# LED_ring_V1.net
KiCad netlist of a schematic drawn in Altium Designer
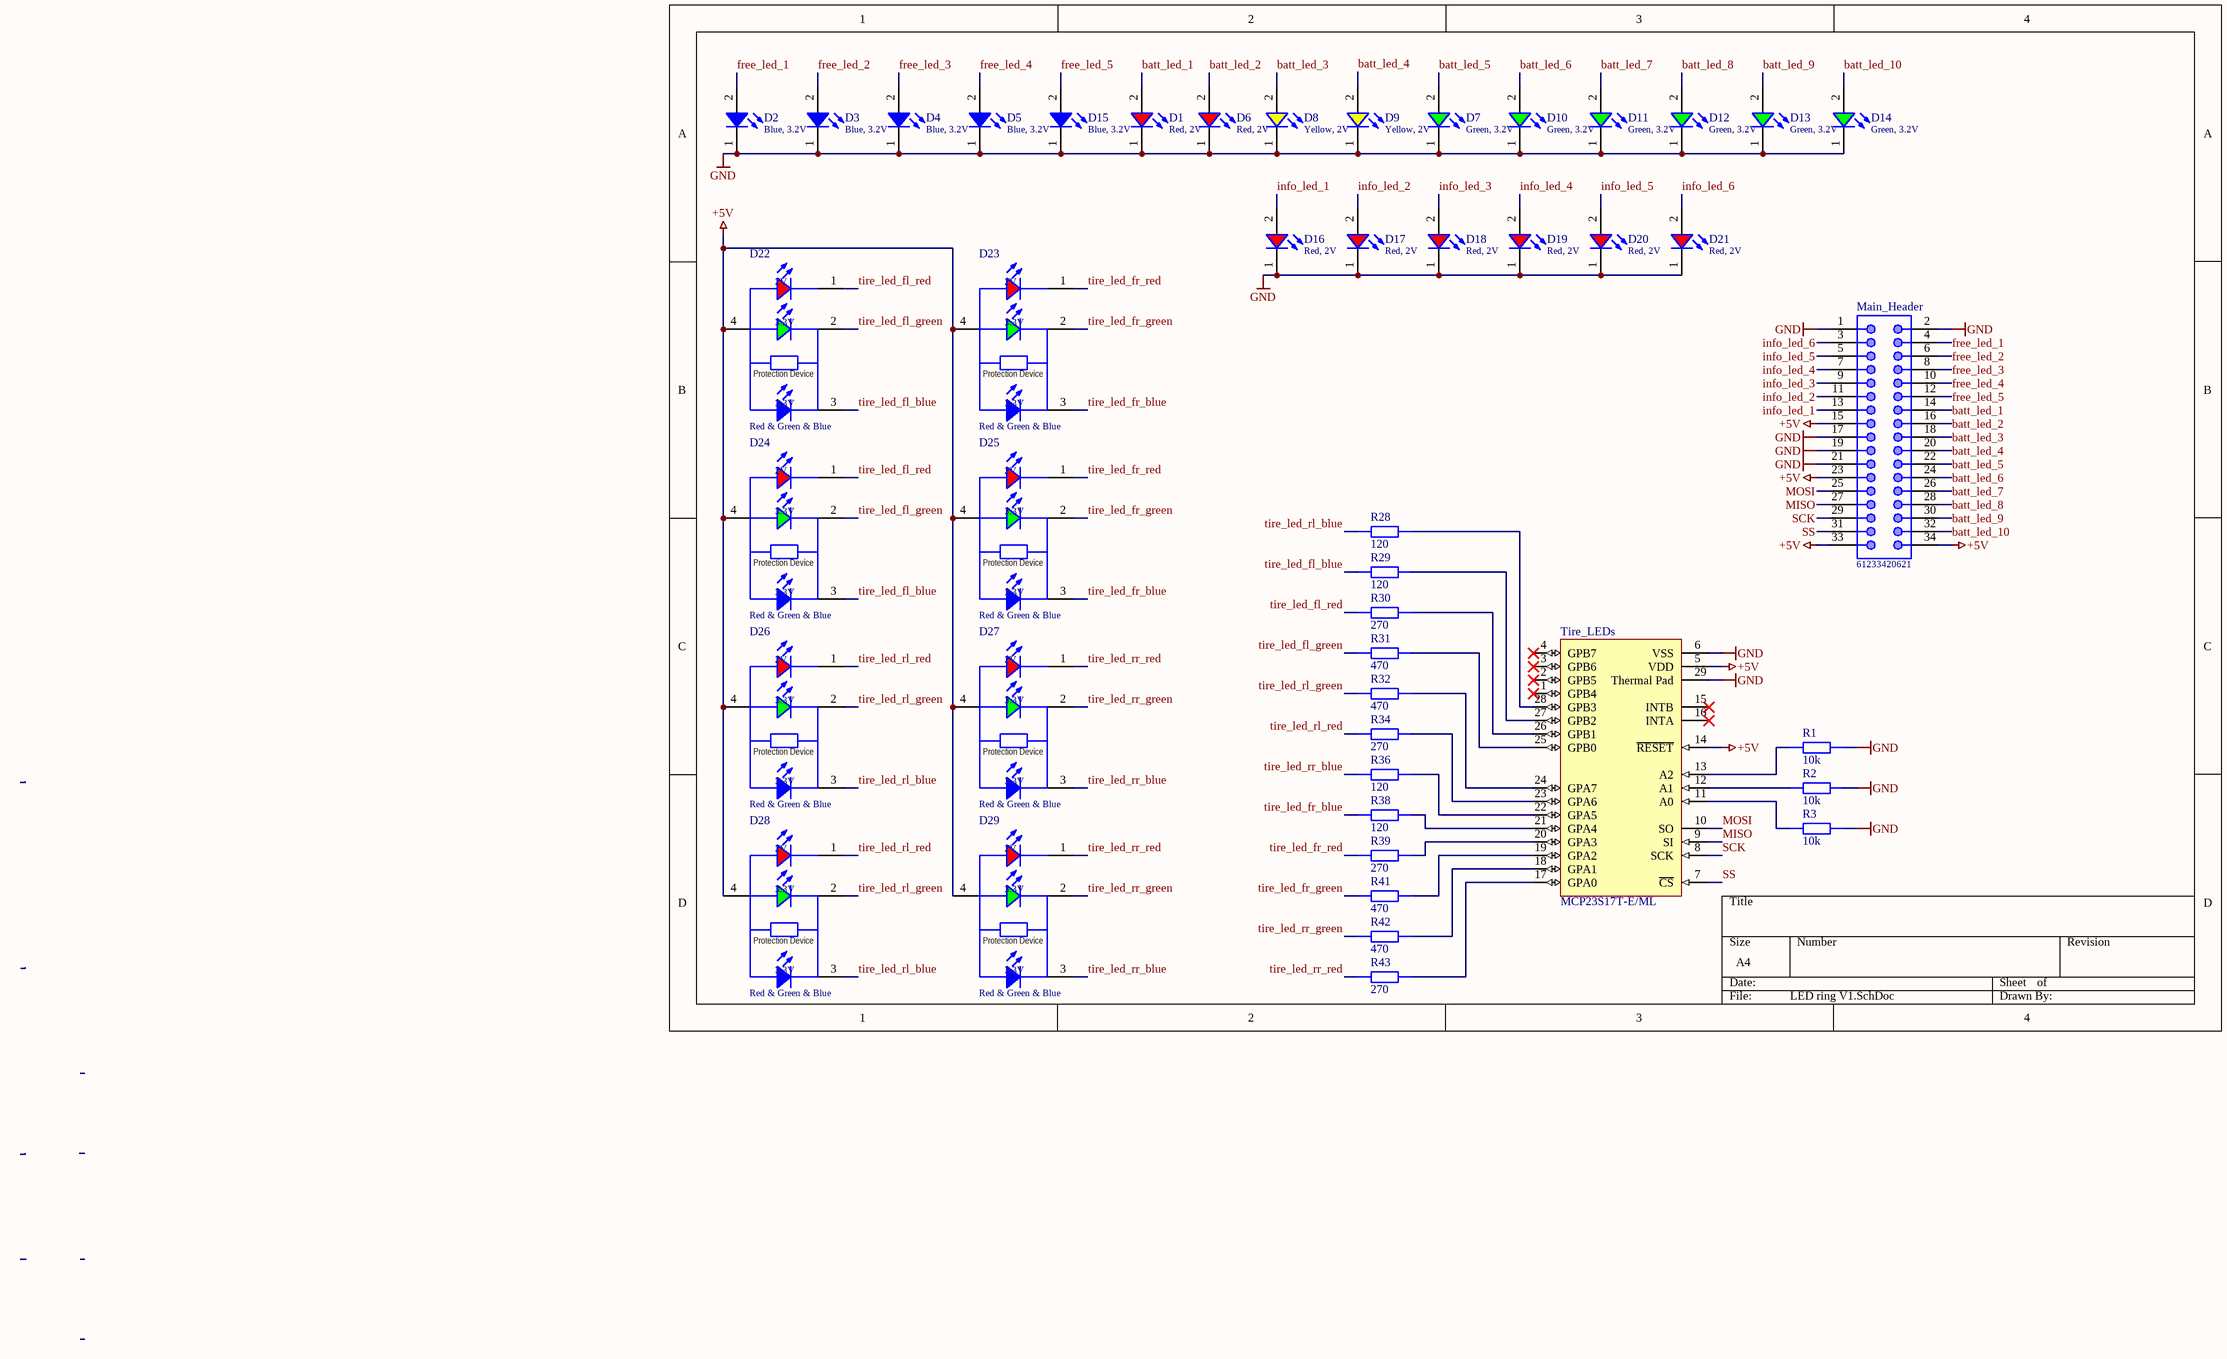
[diagram p0: LED ring V1.SchDoc]

(export (version "E")
  (design (tool "Eeschema 10.0.6"))
  (components
    (comp (ref "D1")
      (value "Red, 2V")
      (footprint "WL-SMCW_0805")
      (description "WL-SMCW SMT Mono-color Chip LED Waterclear, size 0805, Red, 2V, 140deg")
      (fields (field (name "PART NUMBER") "150080RS75000") (field (name "PUBLISHER") "Wurth Elektronik"))
      (libsource (lib "Altium_WL-SMCW (rev20a)") (part "150080RS75000"))
    )
    (comp (ref "D2")
      (value "Blue, 3.2V")
      (footprint "WL-SMCW_0805")
      (description "WL-SMCW SMT Mono-color Chip LED Waterclear, size 0805, Blue, 3.2V, 140deg")
      (fields (field (name "PART NUMBER") "150080BS75000") (field (name "PUBLISHER") "Wurth Elektronik"))
      (libsource (lib "Altium_WL-SMCW (rev20a)") (part "150080BS75000"))
    )
    (comp (ref "D3")
      (value "Blue, 3.2V")
      (footprint "WL-SMCW_0805")
      (description "WL-SMCW SMT Mono-color Chip LED Waterclear, size 0805, Blue, 3.2V, 140deg")
      (fields (field (name "PART NUMBER") "150080BS75000") (field (name "PUBLISHER") "Wurth Elektronik"))
      (libsource (lib "Altium_WL-SMCW (rev20a)") (part "150080BS75000"))
    )
    (comp (ref "D4")
      (value "Blue, 3.2V")
      (footprint "WL-SMCW_0805")
      (description "WL-SMCW SMT Mono-color Chip LED Waterclear, size 0805, Blue, 3.2V, 140deg")
      (fields (field (name "PART NUMBER") "150080BS75000") (field (name "PUBLISHER") "Wurth Elektronik"))
      (libsource (lib "Altium_WL-SMCW (rev20a)") (part "150080BS75000"))
    )
    (comp (ref "D5")
      (value "Blue, 3.2V")
      (footprint "WL-SMCW_0805")
      (description "WL-SMCW SMT Mono-color Chip LED Waterclear, size 0805, Blue, 3.2V, 140deg")
      (fields (field (name "PART NUMBER") "150080BS75000") (field (name "PUBLISHER") "Wurth Elektronik"))
      (libsource (lib "Altium_WL-SMCW (rev20a)") (part "150080BS75000"))
    )
    (comp (ref "D6")
      (value "Red, 2V")
      (footprint "WL-SMCW_0805")
      (description "WL-SMCW SMT Mono-color Chip LED Waterclear, size 0805, Red, 2V, 140deg")
      (fields (field (name "PART NUMBER") "150080RS75000") (field (name "PUBLISHER") "Wurth Elektronik"))
      (libsource (lib "Altium_WL-SMCW (rev20a)") (part "150080RS75000"))
    )
    (comp (ref "D7")
      (value "Green, 3.2V")
      (footprint "WL-SMCW_0805")
      (description "WL-SMCW SMT Mono-color Chip LED Waterclear, size 0805, Green, 3.2V, 140deg")
      (fields (field (name "PART NUMBER") "150080GS75000") (field (name "PUBLISHER") "Wurth Elektronik"))
      (libsource (lib "Altium_WL-SMCW (rev20a)") (part "150080GS75000"))
    )
    (comp (ref "D8")
      (value "Yellow, 2V")
      (footprint "WL-SMCW_0805")
      (description "WL-SMCW SMT Mono-color Chip LED Waterclear, size 0805, Yellow, 2V, 140deg")
      (fields (field (name "PART NUMBER") "150080YS75000") (field (name "PUBLISHER") "Wurth Elektronik"))
      (libsource (lib "Altium_WL-SMCW (rev20a)") (part "150080YS75000"))
    )
    (comp (ref "D9")
      (value "Yellow, 2V")
      (footprint "WL-SMCW_0805")
      (description "WL-SMCW SMT Mono-color Chip LED Waterclear, size 0805, Yellow, 2V, 140deg")
      (fields (field (name "PART NUMBER") "150080YS75000") (field (name "PUBLISHER") "Wurth Elektronik"))
      (libsource (lib "Altium_WL-SMCW (rev20a)") (part "150080YS75000"))
    )
    (comp (ref "D10")
      (value "Green, 3.2V")
      (footprint "WL-SMCW_0805")
      (description "WL-SMCW SMT Mono-color Chip LED Waterclear, size 0805, Green, 3.2V, 140deg")
      (fields (field (name "PART NUMBER") "150080GS75000") (field (name "PUBLISHER") "Wurth Elektronik"))
      (libsource (lib "Altium_WL-SMCW (rev20a)") (part "150080GS75000"))
    )
    (comp (ref "D11")
      (value "Green, 3.2V")
      (footprint "WL-SMCW_0805")
      (description "WL-SMCW SMT Mono-color Chip LED Waterclear, size 0805, Green, 3.2V, 140deg")
      (fields (field (name "PART NUMBER") "150080GS75000") (field (name "PUBLISHER") "Wurth Elektronik"))
      (libsource (lib "Altium_WL-SMCW (rev20a)") (part "150080GS75000"))
    )
    (comp (ref "D12")
      (value "Green, 3.2V")
      (footprint "WL-SMCW_0805")
      (description "WL-SMCW SMT Mono-color Chip LED Waterclear, size 0805, Green, 3.2V, 140deg")
      (fields (field (name "PART NUMBER") "150080GS75000") (field (name "PUBLISHER") "Wurth Elektronik"))
      (libsource (lib "Altium_WL-SMCW (rev20a)") (part "150080GS75000"))
    )
    (comp (ref "D13")
      (value "Green, 3.2V")
      (footprint "WL-SMCW_0805")
      (description "WL-SMCW SMT Mono-color Chip LED Waterclear, size 0805, Green, 3.2V, 140deg")
      (fields (field (name "PART NUMBER") "150080GS75000") (field (name "PUBLISHER") "Wurth Elektronik"))
      (libsource (lib "Altium_WL-SMCW (rev20a)") (part "150080GS75000"))
    )
    (comp (ref "D14")
      (value "Green, 3.2V")
      (footprint "WL-SMCW_0805")
      (description "WL-SMCW SMT Mono-color Chip LED Waterclear, size 0805, Green, 3.2V, 140deg")
      (fields (field (name "PART NUMBER") "150080GS75000") (field (name "PUBLISHER") "Wurth Elektronik"))
      (libsource (lib "Altium_WL-SMCW (rev20a)") (part "150080GS75000"))
    )
    (comp (ref "D15")
      (value "Blue, 3.2V")
      (footprint "WL-SMCW_0805")
      (description "WL-SMCW SMT Mono-color Chip LED Waterclear, size 0805, Blue, 3.2V, 140deg")
      (fields (field (name "PART NUMBER") "150080BS75000") (field (name "PUBLISHER") "Wurth Elektronik"))
      (libsource (lib "Altium_WL-SMCW (rev20a)") (part "150080BS75000"))
    )
    (comp (ref "D16")
      (value "Red, 2V")
      (footprint "WL-SMCW_0805")
      (description "WL-SMCW SMT Mono-color Chip LED Waterclear, size 0805, Red, 2V, 140deg")
      (fields (field (name "PART NUMBER") "150080RS75000") (field (name "PUBLISHER") "Wurth Elektronik"))
      (libsource (lib "Altium_WL-SMCW (rev20a)") (part "150080RS75000"))
    )
    (comp (ref "D17")
      (value "Red, 2V")
      (footprint "WL-SMCW_0805")
      (description "WL-SMCW SMT Mono-color Chip LED Waterclear, size 0805, Red, 2V, 140deg")
      (fields (field (name "PART NUMBER") "150080RS75000") (field (name "PUBLISHER") "Wurth Elektronik"))
      (libsource (lib "Altium_WL-SMCW (rev20a)") (part "150080RS75000"))
    )
    (comp (ref "D18")
      (value "Red, 2V")
      (footprint "WL-SMCW_0805")
      (description "WL-SMCW SMT Mono-color Chip LED Waterclear, size 0805, Red, 2V, 140deg")
      (fields (field (name "PART NUMBER") "150080RS75000") (field (name "PUBLISHER") "Wurth Elektronik"))
      (libsource (lib "Altium_WL-SMCW (rev20a)") (part "150080RS75000"))
    )
    (comp (ref "D19")
      (value "Red, 2V")
      (footprint "WL-SMCW_0805")
      (description "WL-SMCW SMT Mono-color Chip LED Waterclear, size 0805, Red, 2V, 140deg")
      (fields (field (name "PART NUMBER") "150080RS75000") (field (name "PUBLISHER") "Wurth Elektronik"))
      (libsource (lib "Altium_WL-SMCW (rev20a)") (part "150080RS75000"))
    )
    (comp (ref "D20")
      (value "Red, 2V")
      (footprint "WL-SMCW_0805")
      (description "WL-SMCW SMT Mono-color Chip LED Waterclear, size 0805, Red, 2V, 140deg")
      (fields (field (name "PART NUMBER") "150080RS75000") (field (name "PUBLISHER") "Wurth Elektronik"))
      (libsource (lib "Altium_WL-SMCW (rev20a)") (part "150080RS75000"))
    )
    (comp (ref "D21")
      (value "Red, 2V")
      (footprint "WL-SMCW_0805")
      (description "WL-SMCW SMT Mono-color Chip LED Waterclear, size 0805, Red, 2V, 140deg")
      (fields (field (name "PART NUMBER") "150080RS75000") (field (name "PUBLISHER") "Wurth Elektronik"))
      (libsource (lib "Altium_WL-SMCW (rev20a)") (part "150080RS75000"))
    )
    (comp (ref "D22")
      (value "Red & Green & Blue")
      (footprint "WL-SFCW_0805")
      (description "WL-SFCW SMT Full-color Chip LED Waterclear, size 0805, Red & Green & Blue, 120deg")
      (fields (field (name "PART NUMBER") "150080M173000") (field (name "PUBLISHER") "Wurth Elektronik"))
      (libsource (lib "Altium_WL-SFCW (rev19b)") (part "150080M173000"))
    )
    (comp (ref "D23")
      (value "Red & Green & Blue")
      (footprint "WL-SFCW_0805")
      (description "WL-SFCW SMT Full-color Chip LED Waterclear, size 0805, Red & Green & Blue, 120deg")
      (fields (field (name "PART NUMBER") "150080M173000") (field (name "PUBLISHER") "Wurth Elektronik"))
      (libsource (lib "Altium_WL-SFCW (rev19b)") (part "150080M173000"))
    )
    (comp (ref "D24")
      (value "Red & Green & Blue")
      (footprint "WL-SFCW_0805")
      (description "WL-SFCW SMT Full-color Chip LED Waterclear, size 0805, Red & Green & Blue, 120deg")
      (fields (field (name "PART NUMBER") "150080M173000") (field (name "PUBLISHER") "Wurth Elektronik"))
      (libsource (lib "Altium_WL-SFCW (rev19b)") (part "150080M173000"))
    )
    (comp (ref "D25")
      (value "Red & Green & Blue")
      (footprint "WL-SFCW_0805")
      (description "WL-SFCW SMT Full-color Chip LED Waterclear, size 0805, Red & Green & Blue, 120deg")
      (fields (field (name "PART NUMBER") "150080M173000") (field (name "PUBLISHER") "Wurth Elektronik"))
      (libsource (lib "Altium_WL-SFCW (rev19b)") (part "150080M173000"))
    )
    (comp (ref "D26")
      (value "Red & Green & Blue")
      (footprint "WL-SFCW_0805")
      (description "WL-SFCW SMT Full-color Chip LED Waterclear, size 0805, Red & Green & Blue, 120deg")
      (fields (field (name "PART NUMBER") "150080M173000") (field (name "PUBLISHER") "Wurth Elektronik"))
      (libsource (lib "Altium_WL-SFCW (rev19b)") (part "150080M173000"))
    )
    (comp (ref "D27")
      (value "Red & Green & Blue")
      (footprint "WL-SFCW_0805")
      (description "WL-SFCW SMT Full-color Chip LED Waterclear, size 0805, Red & Green & Blue, 120deg")
      (fields (field (name "PART NUMBER") "150080M173000") (field (name "PUBLISHER") "Wurth Elektronik"))
      (libsource (lib "Altium_WL-SFCW (rev19b)") (part "150080M173000"))
    )
    (comp (ref "D28")
      (value "Red & Green & Blue")
      (footprint "WL-SFCW_0805")
      (description "WL-SFCW SMT Full-color Chip LED Waterclear, size 0805, Red & Green & Blue, 120deg")
      (fields (field (name "PART NUMBER") "150080M173000") (field (name "PUBLISHER") "Wurth Elektronik"))
      (libsource (lib "Altium_WL-SFCW (rev19b)") (part "150080M173000"))
    )
    (comp (ref "D29")
      (value "Red & Green & Blue")
      (footprint "WL-SFCW_0805")
      (description "WL-SFCW SMT Full-color Chip LED Waterclear, size 0805, Red & Green & Blue, 120deg")
      (fields (field (name "PART NUMBER") "150080M173000") (field (name "PUBLISHER") "Wurth Elektronik"))
      (libsource (lib "Altium_WL-SFCW (rev19b)") (part "150080M173000"))
    )
    (comp (ref "Main_Header")
      (value "61233420621")
      (footprint "61233420621")
      (description "WR-BHD Box Header, Male PCB side, pitch 2.54mm, SMT, Straight, 34p")
      (fields (field (name "MANUFACTURER") "Wurth Elektronik"))
      (libsource (lib "Altium_WR-BHD (rev21a)") (part "61233420621"))
    )
    (comp (ref "R1")
      (value "10k")
      (footprint "STACKPOLE CSR0603")
      (description "Resistor with multiple footprints")
      (fields (field (name "Comment") "SMD Resistor"))
      (libsource (lib "Standardbauteile") (part "SMD Resistor"))
    )
    (comp (ref "R2")
      (value "10k")
      (footprint "STACKPOLE CSR0603")
      (description "Resistor with multiple footprints")
      (fields (field (name "Comment") "SMD Resistor"))
      (libsource (lib "Standardbauteile") (part "SMD Resistor"))
    )
    (comp (ref "R3")
      (value "10k")
      (footprint "STACKPOLE CSR0603")
      (description "Resistor with multiple footprints")
      (fields (field (name "Comment") "SMD Resistor"))
      (libsource (lib "Standardbauteile") (part "SMD Resistor"))
    )
    (comp (ref "R28")
      (value "120")
      (footprint "STACKPOLE CSR0603")
      (description "Resistor with multiple footprints")
      (fields (field (name "Comment") "SMD Resistor"))
      (libsource (lib "Standardbauteile") (part "SMD Resistor"))
    )
    (comp (ref "R29")
      (value "120")
      (footprint "STACKPOLE CSR0603")
      (description "Resistor with multiple footprints")
      (fields (field (name "Comment") "SMD Resistor"))
      (libsource (lib "Standardbauteile") (part "SMD Resistor"))
    )
    (comp (ref "R30")
      (value "270")
      (footprint "STACKPOLE CSR0603")
      (description "Resistor with multiple footprints")
      (fields (field (name "Comment") "SMD Resistor"))
      (libsource (lib "Standardbauteile") (part "SMD Resistor"))
    )
    (comp (ref "R31")
      (value "470")
      (footprint "STACKPOLE CSR0603")
      (description "Resistor with multiple footprints")
      (fields (field (name "Comment") "SMD Resistor"))
      (libsource (lib "Standardbauteile") (part "SMD Resistor"))
    )
    (comp (ref "R32")
      (value "470")
      (footprint "STACKPOLE CSR0603")
      (description "Resistor with multiple footprints")
      (fields (field (name "Comment") "SMD Resistor"))
      (libsource (lib "Standardbauteile") (part "SMD Resistor"))
    )
    (comp (ref "R34")
      (value "270")
      (footprint "STACKPOLE CSR0603")
      (description "Resistor with multiple footprints")
      (fields (field (name "Comment") "SMD Resistor"))
      (libsource (lib "Standardbauteile") (part "SMD Resistor"))
    )
    (comp (ref "R36")
      (value "120")
      (footprint "STACKPOLE CSR0603")
      (description "Resistor with multiple footprints")
      (fields (field (name "Comment") "SMD Resistor"))
      (libsource (lib "Standardbauteile") (part "SMD Resistor"))
    )
    (comp (ref "R38")
      (value "120")
      (footprint "STACKPOLE CSR0603")
      (description "Resistor with multiple footprints")
      (fields (field (name "Comment") "SMD Resistor"))
      (libsource (lib "Standardbauteile") (part "SMD Resistor"))
    )
    (comp (ref "R39")
      (value "270")
      (footprint "STACKPOLE CSR0603")
      (description "Resistor with multiple footprints")
      (fields (field (name "Comment") "SMD Resistor"))
      (libsource (lib "Standardbauteile") (part "SMD Resistor"))
    )
    (comp (ref "R41")
      (value "470")
      (footprint "STACKPOLE CSR0603")
      (description "Resistor with multiple footprints")
      (fields (field (name "Comment") "SMD Resistor"))
      (libsource (lib "Standardbauteile") (part "SMD Resistor"))
    )
    (comp (ref "R42")
      (value "470")
      (footprint "STACKPOLE CSR0603")
      (description "Resistor with multiple footprints")
      (fields (field (name "Comment") "SMD Resistor"))
      (libsource (lib "Standardbauteile") (part "SMD Resistor"))
    )
    (comp (ref "R43")
      (value "270")
      (footprint "STACKPOLE CSR0603")
      (description "Resistor with multiple footprints")
      (fields (field (name "Comment") "SMD Resistor"))
      (libsource (lib "Standardbauteile") (part "SMD Resistor"))
    )
    (comp (ref "Tire_LEDs")
      (value "MCP23S17T-E/ML")
      (footprint "QFN-ML28_M")
      (description "16-Bit I/O Expander with Serial Interface, 28-Pin QFN, Extended Temperature, Tape and Reel")
      (libsource (lib "Altium Content Vault") (part "PR-BUSIC-MCP23S17-29"))
    )
  )
  (nets
    (net (code "1") (name "+5V") (class "Default")
      (node (ref "D22") (pin "4") (pinfunction "A_4") (pintype "passive"))
      (node (ref "D23") (pin "4") (pinfunction "A_4") (pintype "passive"))
      (node (ref "D24") (pin "4") (pinfunction "A_4") (pintype "passive"))
      (node (ref "D25") (pin "4") (pinfunction "A_4") (pintype "passive"))
      (node (ref "D26") (pin "4") (pinfunction "A_4") (pintype "passive"))
      (node (ref "D27") (pin "4") (pinfunction "A_4") (pintype "passive"))
      (node (ref "D28") (pin "4") (pinfunction "A_4") (pintype "passive"))
      (node (ref "D29") (pin "4") (pinfunction "A_4") (pintype "passive"))
      (node (ref "Main_Header") (pin "15") (pinfunction "15_15") (pintype "passive"))
      (node (ref "Main_Header") (pin "23") (pinfunction "23_23") (pintype "passive"))
      (node (ref "Main_Header") (pin "33") (pinfunction "33_33") (pintype "passive"))
      (node (ref "Main_Header") (pin "34") (pinfunction "34_34") (pintype "passive"))
      (node (ref "Tire_LEDs") (pin "14") (pinfunction "~{RESET}_14") (pintype "input"))
      (node (ref "Tire_LEDs") (pin "5") (pinfunction "VDD_5") (pintype "power_in"))
    )
    (net (code "2") (name "/MISO") (class "Default")
      (node (ref "Main_Header") (pin "27") (pinfunction "27_27") (pintype "passive"))
      (node (ref "Tire_LEDs") (pin "9") (pinfunction "SI_9") (pintype "input"))
    )
    (net (code "3") (name "/MOSI") (class "Default")
      (node (ref "Main_Header") (pin "25") (pinfunction "25_25") (pintype "passive"))
      (node (ref "Tire_LEDs") (pin "10") (pinfunction "SO_10") (pintype "tri_state"))
    )
    (net (code "4") (name "/SCK") (class "Default")
      (node (ref "Main_Header") (pin "29") (pinfunction "29_29") (pintype "passive"))
      (node (ref "Tire_LEDs") (pin "8") (pinfunction "SCK_8") (pintype "input"))
    )
    (net (code "5") (name "/SS") (class "Default")
      (node (ref "Main_Header") (pin "31") (pinfunction "31_31") (pintype "passive"))
      (node (ref "Tire_LEDs") (pin "7") (pinfunction "~{CS}_7") (pintype "input"))
    )
    (net (code "6") (name "/batt_led_1") (class "Default")
      (node (ref "D1") (pin "2") (pinfunction "A_2") (pintype "passive"))
      (node (ref "Main_Header") (pin "14") (pinfunction "14_14") (pintype "passive"))
    )
    (net (code "7") (name "/batt_led_2") (class "Default")
      (node (ref "D6") (pin "2") (pinfunction "A_2") (pintype "passive"))
      (node (ref "Main_Header") (pin "16") (pinfunction "16_16") (pintype "passive"))
    )
    (net (code "8") (name "/batt_led_3") (class "Default")
      (node (ref "D8") (pin "2") (pinfunction "A_2") (pintype "passive"))
      (node (ref "Main_Header") (pin "18") (pinfunction "18_18") (pintype "passive"))
    )
    (net (code "9") (name "/batt_led_4") (class "Default")
      (node (ref "D9") (pin "2") (pinfunction "A_2") (pintype "passive"))
      (node (ref "Main_Header") (pin "20") (pinfunction "20_20") (pintype "passive"))
    )
    (net (code "10") (name "/batt_led_5") (class "Default")
      (node (ref "D7") (pin "2") (pinfunction "A_2") (pintype "passive"))
      (node (ref "Main_Header") (pin "22") (pinfunction "22_22") (pintype "passive"))
    )
    (net (code "11") (name "/batt_led_6") (class "Default")
      (node (ref "D10") (pin "2") (pinfunction "A_2") (pintype "passive"))
      (node (ref "Main_Header") (pin "24") (pinfunction "24_24") (pintype "passive"))
    )
    (net (code "12") (name "/batt_led_7") (class "Default")
      (node (ref "D11") (pin "2") (pinfunction "A_2") (pintype "passive"))
      (node (ref "Main_Header") (pin "26") (pinfunction "26_26") (pintype "passive"))
    )
    (net (code "13") (name "/batt_led_8") (class "Default")
      (node (ref "D12") (pin "2") (pinfunction "A_2") (pintype "passive"))
      (node (ref "Main_Header") (pin "28") (pinfunction "28_28") (pintype "passive"))
    )
    (net (code "14") (name "/batt_led_9") (class "Default")
      (node (ref "D13") (pin "2") (pinfunction "A_2") (pintype "passive"))
      (node (ref "Main_Header") (pin "30") (pinfunction "30_30") (pintype "passive"))
    )
    (net (code "15") (name "/batt_led_10") (class "Default")
      (node (ref "D14") (pin "2") (pinfunction "A_2") (pintype "passive"))
      (node (ref "Main_Header") (pin "32") (pinfunction "32_32") (pintype "passive"))
    )
    (net (code "16") (name "/free_led_1") (class "Default")
      (node (ref "D2") (pin "2") (pinfunction "A_2") (pintype "passive"))
      (node (ref "Main_Header") (pin "4") (pinfunction "4_4") (pintype "passive"))
    )
    (net (code "17") (name "/free_led_2") (class "Default")
      (node (ref "D3") (pin "2") (pinfunction "A_2") (pintype "passive"))
      (node (ref "Main_Header") (pin "6") (pinfunction "6_6") (pintype "passive"))
    )
    (net (code "18") (name "/free_led_3") (class "Default")
      (node (ref "D4") (pin "2") (pinfunction "A_2") (pintype "passive"))
      (node (ref "Main_Header") (pin "8") (pinfunction "8_8") (pintype "passive"))
    )
    (net (code "19") (name "/free_led_4") (class "Default")
      (node (ref "D5") (pin "2") (pinfunction "A_2") (pintype "passive"))
      (node (ref "Main_Header") (pin "10") (pinfunction "10_10") (pintype "passive"))
    )
    (net (code "20") (name "/free_led_5") (class "Default")
      (node (ref "D15") (pin "2") (pinfunction "A_2") (pintype "passive"))
      (node (ref "Main_Header") (pin "12") (pinfunction "12_12") (pintype "passive"))
    )
    (net (code "21") (name "/info_led_1") (class "Default")
      (node (ref "D16") (pin "2") (pinfunction "A_2") (pintype "passive"))
      (node (ref "Main_Header") (pin "13") (pinfunction "13_13") (pintype "passive"))
    )
    (net (code "22") (name "/info_led_2") (class "Default")
      (node (ref "D17") (pin "2") (pinfunction "A_2") (pintype "passive"))
      (node (ref "Main_Header") (pin "11") (pinfunction "11_11") (pintype "passive"))
    )
    (net (code "23") (name "/info_led_3") (class "Default")
      (node (ref "D18") (pin "2") (pinfunction "A_2") (pintype "passive"))
      (node (ref "Main_Header") (pin "9") (pinfunction "9_9") (pintype "passive"))
    )
    (net (code "24") (name "/info_led_4") (class "Default")
      (node (ref "D19") (pin "2") (pinfunction "A_2") (pintype "passive"))
      (node (ref "Main_Header") (pin "7") (pinfunction "7_7") (pintype "passive"))
    )
    (net (code "25") (name "/info_led_5") (class "Default")
      (node (ref "D20") (pin "2") (pinfunction "A_2") (pintype "passive"))
      (node (ref "Main_Header") (pin "5") (pinfunction "5_5") (pintype "passive"))
    )
    (net (code "26") (name "/info_led_6") (class "Default")
      (node (ref "D21") (pin "2") (pinfunction "A_2") (pintype "passive"))
      (node (ref "Main_Header") (pin "3") (pinfunction "3_3") (pintype "passive"))
    )
    (net (code "27") (name "/tire_led_fl_blue") (class "Default")
      (node (ref "D22") (pin "3") (pinfunction "K_3") (pintype "passive"))
      (node (ref "D24") (pin "3") (pinfunction "K_3") (pintype "passive"))
      (node (ref "R29") (pin "2") (pinfunction "2_2") (pintype "passive"))
    )
    (net (code "28") (name "/tire_led_fl_green") (class "Default")
      (node (ref "D22") (pin "2") (pinfunction "K_2") (pintype "passive"))
      (node (ref "D24") (pin "2") (pinfunction "K_2") (pintype "passive"))
      (node (ref "R31") (pin "2") (pinfunction "2_2") (pintype "passive"))
    )
    (net (code "29") (name "/tire_led_fl_red") (class "Default")
      (node (ref "D22") (pin "1") (pinfunction "K_1") (pintype "passive"))
      (node (ref "D24") (pin "1") (pinfunction "K_1") (pintype "passive"))
      (node (ref "R30") (pin "2") (pinfunction "2_2") (pintype "passive"))
    )
    (net (code "30") (name "/tire_led_fr_blue") (class "Default")
      (node (ref "D23") (pin "3") (pinfunction "K_3") (pintype "passive"))
      (node (ref "D25") (pin "3") (pinfunction "K_3") (pintype "passive"))
      (node (ref "R38") (pin "2") (pinfunction "2_2") (pintype "passive"))
    )
    (net (code "31") (name "/tire_led_fr_green") (class "Default")
      (node (ref "D23") (pin "2") (pinfunction "K_2") (pintype "passive"))
      (node (ref "D25") (pin "2") (pinfunction "K_2") (pintype "passive"))
      (node (ref "R41") (pin "2") (pinfunction "2_2") (pintype "passive"))
    )
    (net (code "32") (name "/tire_led_fr_red") (class "Default")
      (node (ref "D23") (pin "1") (pinfunction "K_1") (pintype "passive"))
      (node (ref "D25") (pin "1") (pinfunction "K_1") (pintype "passive"))
      (node (ref "R39") (pin "2") (pinfunction "2_2") (pintype "passive"))
    )
    (net (code "33") (name "/tire_led_rl_blue") (class "Default")
      (node (ref "D26") (pin "3") (pinfunction "K_3") (pintype "passive"))
      (node (ref "D28") (pin "3") (pinfunction "K_3") (pintype "passive"))
      (node (ref "R28") (pin "2") (pinfunction "2_2") (pintype "passive"))
    )
    (net (code "34") (name "/tire_led_rl_green") (class "Default")
      (node (ref "D26") (pin "2") (pinfunction "K_2") (pintype "passive"))
      (node (ref "D28") (pin "2") (pinfunction "K_2") (pintype "passive"))
      (node (ref "R32") (pin "2") (pinfunction "2_2") (pintype "passive"))
    )
    (net (code "35") (name "/tire_led_rl_red") (class "Default")
      (node (ref "D26") (pin "1") (pinfunction "K_1") (pintype "passive"))
      (node (ref "D28") (pin "1") (pinfunction "K_1") (pintype "passive"))
      (node (ref "R34") (pin "2") (pinfunction "2_2") (pintype "passive"))
    )
    (net (code "36") (name "/tire_led_rr_blue") (class "Default")
      (node (ref "D27") (pin "3") (pinfunction "K_3") (pintype "passive"))
      (node (ref "D29") (pin "3") (pinfunction "K_3") (pintype "passive"))
      (node (ref "R36") (pin "2") (pinfunction "2_2") (pintype "passive"))
    )
    (net (code "37") (name "/tire_led_rr_green") (class "Default")
      (node (ref "D27") (pin "2") (pinfunction "K_2") (pintype "passive"))
      (node (ref "D29") (pin "2") (pinfunction "K_2") (pintype "passive"))
      (node (ref "R42") (pin "2") (pinfunction "2_2") (pintype "passive"))
    )
    (net (code "38") (name "/tire_led_rr_red") (class "Default")
      (node (ref "D27") (pin "1") (pinfunction "K_1") (pintype "passive"))
      (node (ref "D29") (pin "1") (pinfunction "K_1") (pintype "passive"))
      (node (ref "R43") (pin "2") (pinfunction "2_2") (pintype "passive"))
    )
    (net (code "39") (name "GND") (class "Default")
      (node (ref "D1") (pin "1") (pinfunction "K_1") (pintype "passive"))
      (node (ref "D10") (pin "1") (pinfunction "K_1") (pintype "passive"))
      (node (ref "D11") (pin "1") (pinfunction "K_1") (pintype "passive"))
      (node (ref "D12") (pin "1") (pinfunction "K_1") (pintype "passive"))
      (node (ref "D13") (pin "1") (pinfunction "K_1") (pintype "passive"))
      (node (ref "D14") (pin "1") (pinfunction "K_1") (pintype "passive"))
      (node (ref "D15") (pin "1") (pinfunction "K_1") (pintype "passive"))
      (node (ref "D16") (pin "1") (pinfunction "K_1") (pintype "passive"))
      (node (ref "D17") (pin "1") (pinfunction "K_1") (pintype "passive"))
      (node (ref "D18") (pin "1") (pinfunction "K_1") (pintype "passive"))
      (node (ref "D19") (pin "1") (pinfunction "K_1") (pintype "passive"))
      (node (ref "D2") (pin "1") (pinfunction "K_1") (pintype "passive"))
      (node (ref "D20") (pin "1") (pinfunction "K_1") (pintype "passive"))
      (node (ref "D21") (pin "1") (pinfunction "K_1") (pintype "passive"))
      (node (ref "D3") (pin "1") (pinfunction "K_1") (pintype "passive"))
      (node (ref "D4") (pin "1") (pinfunction "K_1") (pintype "passive"))
      (node (ref "D5") (pin "1") (pinfunction "K_1") (pintype "passive"))
      (node (ref "D6") (pin "1") (pinfunction "K_1") (pintype "passive"))
      (node (ref "D7") (pin "1") (pinfunction "K_1") (pintype "passive"))
      (node (ref "D8") (pin "1") (pinfunction "K_1") (pintype "passive"))
      (node (ref "D9") (pin "1") (pinfunction "K_1") (pintype "passive"))
      (node (ref "Main_Header") (pin "1") (pinfunction "1_1") (pintype "passive"))
      (node (ref "Main_Header") (pin "17") (pinfunction "17_17") (pintype "passive"))
      (node (ref "Main_Header") (pin "19") (pinfunction "19_19") (pintype "passive"))
      (node (ref "Main_Header") (pin "2") (pinfunction "2_2") (pintype "passive"))
      (node (ref "Main_Header") (pin "21") (pinfunction "21_21") (pintype "passive"))
      (node (ref "R1") (pin "2") (pinfunction "2_2") (pintype "passive"))
      (node (ref "R2") (pin "2") (pinfunction "2_2") (pintype "passive"))
      (node (ref "R3") (pin "2") (pinfunction "2_2") (pintype "passive"))
      (node (ref "Tire_LEDs") (pin "29") (pinfunction "Thermal_Pad_29") (pintype "passive"))
      (node (ref "Tire_LEDs") (pin "6") (pinfunction "VSS_6") (pintype "power_in"))
    )
    (net (code "40") (name "Net-(Tire_LEDs-A0)") (class "Default")
      (node (ref "R3") (pin "1") (pinfunction "1_1") (pintype "passive"))
      (node (ref "Tire_LEDs") (pin "11") (pinfunction "A0_11") (pintype "input"))
    )
    (net (code "41") (name "Net-(Tire_LEDs-A1)") (class "Default")
      (node (ref "R2") (pin "1") (pinfunction "1_1") (pintype "passive"))
      (node (ref "Tire_LEDs") (pin "12") (pinfunction "A1_12") (pintype "input"))
    )
    (net (code "42") (name "Net-(Tire_LEDs-A2)") (class "Default")
      (node (ref "R1") (pin "1") (pinfunction "1_1") (pintype "passive"))
      (node (ref "Tire_LEDs") (pin "13") (pinfunction "A2_13") (pintype "input"))
    )
    (net (code "43") (name "Net-(Tire_LEDs-GPA0)") (class "Default")
      (node (ref "R43") (pin "1") (pinfunction "1_1") (pintype "passive"))
      (node (ref "Tire_LEDs") (pin "17") (pinfunction "GPA0_17") (pintype "bidirectional"))
    )
    (net (code "44") (name "Net-(Tire_LEDs-GPA1)") (class "Default")
      (node (ref "R42") (pin "1") (pinfunction "1_1") (pintype "passive"))
      (node (ref "Tire_LEDs") (pin "18") (pinfunction "GPA1_18") (pintype "bidirectional"))
    )
    (net (code "45") (name "Net-(Tire_LEDs-GPA2)") (class "Default")
      (node (ref "R41") (pin "1") (pinfunction "1_1") (pintype "passive"))
      (node (ref "Tire_LEDs") (pin "19") (pinfunction "GPA2_19") (pintype "bidirectional"))
    )
    (net (code "46") (name "Net-(Tire_LEDs-GPA3)") (class "Default")
      (node (ref "R39") (pin "1") (pinfunction "1_1") (pintype "passive"))
      (node (ref "Tire_LEDs") (pin "20") (pinfunction "GPA3_20") (pintype "bidirectional"))
    )
    (net (code "47") (name "Net-(Tire_LEDs-GPA4)") (class "Default")
      (node (ref "R38") (pin "1") (pinfunction "1_1") (pintype "passive"))
      (node (ref "Tire_LEDs") (pin "21") (pinfunction "GPA4_21") (pintype "bidirectional"))
    )
    (net (code "48") (name "Net-(Tire_LEDs-GPA5)") (class "Default")
      (node (ref "R36") (pin "1") (pinfunction "1_1") (pintype "passive"))
      (node (ref "Tire_LEDs") (pin "22") (pinfunction "GPA5_22") (pintype "bidirectional"))
    )
    (net (code "49") (name "Net-(Tire_LEDs-GPA6)") (class "Default")
      (node (ref "R34") (pin "1") (pinfunction "1_1") (pintype "passive"))
      (node (ref "Tire_LEDs") (pin "23") (pinfunction "GPA6_23") (pintype "bidirectional"))
    )
    (net (code "50") (name "Net-(Tire_LEDs-GPA7)") (class "Default")
      (node (ref "R32") (pin "1") (pinfunction "1_1") (pintype "passive"))
      (node (ref "Tire_LEDs") (pin "24") (pinfunction "GPA7_24") (pintype "bidirectional"))
    )
    (net (code "51") (name "Net-(Tire_LEDs-GPB0)") (class "Default")
      (node (ref "R31") (pin "1") (pinfunction "1_1") (pintype "passive"))
      (node (ref "Tire_LEDs") (pin "25") (pinfunction "GPB0_25") (pintype "bidirectional"))
    )
    (net (code "52") (name "Net-(Tire_LEDs-GPB1)") (class "Default")
      (node (ref "R30") (pin "1") (pinfunction "1_1") (pintype "passive"))
      (node (ref "Tire_LEDs") (pin "26") (pinfunction "GPB1_26") (pintype "bidirectional"))
    )
    (net (code "53") (name "Net-(Tire_LEDs-GPB2)") (class "Default")
      (node (ref "R29") (pin "1") (pinfunction "1_1") (pintype "passive"))
      (node (ref "Tire_LEDs") (pin "27") (pinfunction "GPB2_27") (pintype "bidirectional"))
    )
    (net (code "54") (name "Net-(Tire_LEDs-GPB3)") (class "Default")
      (node (ref "R28") (pin "1") (pinfunction "1_1") (pintype "passive"))
      (node (ref "Tire_LEDs") (pin "28") (pinfunction "GPB3_28") (pintype "bidirectional"))
    )
    (net (code "55") (name "unconnected-(Tire_LEDs-GPB4-Pad1)") (class "Default")
      (node (ref "Tire_LEDs") (pin "1") (pinfunction "GPB4_1") (pintype "bidirectional+no_connect"))
    )
    (net (code "56") (name "unconnected-(Tire_LEDs-GPB5-Pad2)") (class "Default")
      (node (ref "Tire_LEDs") (pin "2") (pinfunction "GPB5_2") (pintype "bidirectional+no_connect"))
    )
    (net (code "57") (name "unconnected-(Tire_LEDs-GPB6-Pad3)") (class "Default")
      (node (ref "Tire_LEDs") (pin "3") (pinfunction "GPB6_3") (pintype "bidirectional+no_connect"))
    )
    (net (code "58") (name "unconnected-(Tire_LEDs-GPB7-Pad4)") (class "Default")
      (node (ref "Tire_LEDs") (pin "4") (pinfunction "GPB7_4") (pintype "bidirectional+no_connect"))
    )
    (net (code "59") (name "unconnected-(Tire_LEDs-INTA-Pad16)") (class "Default")
      (node (ref "Tire_LEDs") (pin "16") (pinfunction "INTA_16") (pintype "open_collector+no_connect"))
    )
    (net (code "60") (name "unconnected-(Tire_LEDs-INTB-Pad15)") (class "Default")
      (node (ref "Tire_LEDs") (pin "15") (pinfunction "INTB_15") (pintype "open_collector+no_connect"))
    )
  )
)
